# untitled.net
KiCad netlist of a schematic drawn in EAGLE
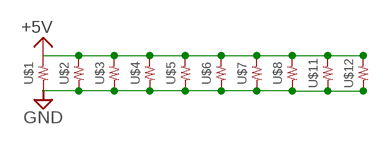
[diagram p0: schematic, sheet 1]

(export (version "E")
  (design (tool "Eeschema 10.0.6"))
  (components
    (comp (ref "U$1")
      (value "RESISTOR__SMD")
      (footprint "eagle-import:1608")
      (libsource (lib "eagle-import") (part "RESISTOR__SMD"))
    )
    (comp (ref "U$2")
      (value "RESISTOR__SMD")
      (footprint "eagle-import:1608")
      (libsource (lib "eagle-import") (part "RESISTOR__SMD"))
    )
    (comp (ref "U$3")
      (value "RESISTOR__SMD")
      (footprint "eagle-import:1608")
      (libsource (lib "eagle-import") (part "RESISTOR__SMD"))
    )
    (comp (ref "U$4")
      (value "RESISTOR__SMD")
      (footprint "eagle-import:1608")
      (libsource (lib "eagle-import") (part "RESISTOR__SMD"))
    )
    (comp (ref "U$5")
      (value "RESISTOR__SMD")
      (footprint "eagle-import:1608")
      (libsource (lib "eagle-import") (part "RESISTOR__SMD"))
    )
    (comp (ref "U$6")
      (value "RESISTOR__SMD")
      (footprint "eagle-import:1608")
      (libsource (lib "eagle-import") (part "RESISTOR__SMD"))
    )
    (comp (ref "U$7")
      (value "RESISTOR__SMD")
      (footprint "eagle-import:1608")
      (libsource (lib "eagle-import") (part "RESISTOR__SMD"))
    )
    (comp (ref "U$8")
      (value "RESISTOR__SMD")
      (footprint "eagle-import:1608")
      (libsource (lib "eagle-import") (part "RESISTOR__SMD"))
    )
    (comp (ref "U$11")
      (value "RESISTOR__SMD")
      (footprint "eagle-import:1608")
      (libsource (lib "eagle-import") (part "RESISTOR__SMD"))
    )
    (comp (ref "U$12")
      (value "RESISTOR__SMD")
      (footprint "eagle-import:1608")
      (libsource (lib "eagle-import") (part "RESISTOR__SMD"))
    )
  )
  (nets
    (net (code "1") (name "+5V") (class "Default")
      (node (ref "U$1") (pin "2") (pinfunction "P$2_2") (pintype "passive"))
      (node (ref "U$11") (pin "2") (pinfunction "P$2_2") (pintype "passive"))
      (node (ref "U$12") (pin "2") (pinfunction "P$2_2") (pintype "passive"))
      (node (ref "U$2") (pin "2") (pinfunction "P$2_2") (pintype "passive"))
      (node (ref "U$3") (pin "2") (pinfunction "P$2_2") (pintype "passive"))
      (node (ref "U$4") (pin "2") (pinfunction "P$2_2") (pintype "passive"))
      (node (ref "U$5") (pin "2") (pinfunction "P$2_2") (pintype "passive"))
      (node (ref "U$6") (pin "2") (pinfunction "P$2_2") (pintype "passive"))
      (node (ref "U$7") (pin "2") (pinfunction "P$2_2") (pintype "passive"))
      (node (ref "U$8") (pin "2") (pinfunction "P$2_2") (pintype "passive"))
    )
    (net (code "2") (name "GND") (class "Default")
      (node (ref "U$1") (pin "1") (pinfunction "P$1_1") (pintype "passive"))
      (node (ref "U$11") (pin "1") (pinfunction "P$1_1") (pintype "passive"))
      (node (ref "U$12") (pin "1") (pinfunction "P$1_1") (pintype "passive"))
      (node (ref "U$2") (pin "1") (pinfunction "P$1_1") (pintype "passive"))
      (node (ref "U$3") (pin "1") (pinfunction "P$1_1") (pintype "passive"))
      (node (ref "U$4") (pin "1") (pinfunction "P$1_1") (pintype "passive"))
      (node (ref "U$5") (pin "1") (pinfunction "P$1_1") (pintype "passive"))
      (node (ref "U$6") (pin "1") (pinfunction "P$1_1") (pintype "passive"))
      (node (ref "U$7") (pin "1") (pinfunction "P$1_1") (pintype "passive"))
      (node (ref "U$8") (pin "1") (pinfunction "P$1_1") (pintype "passive"))
    )
  )
)
